# ProPrj_Circular_Weaving_2025-12-15.net
KiCad netlist of a schematic drawn in EasyEDA Pro
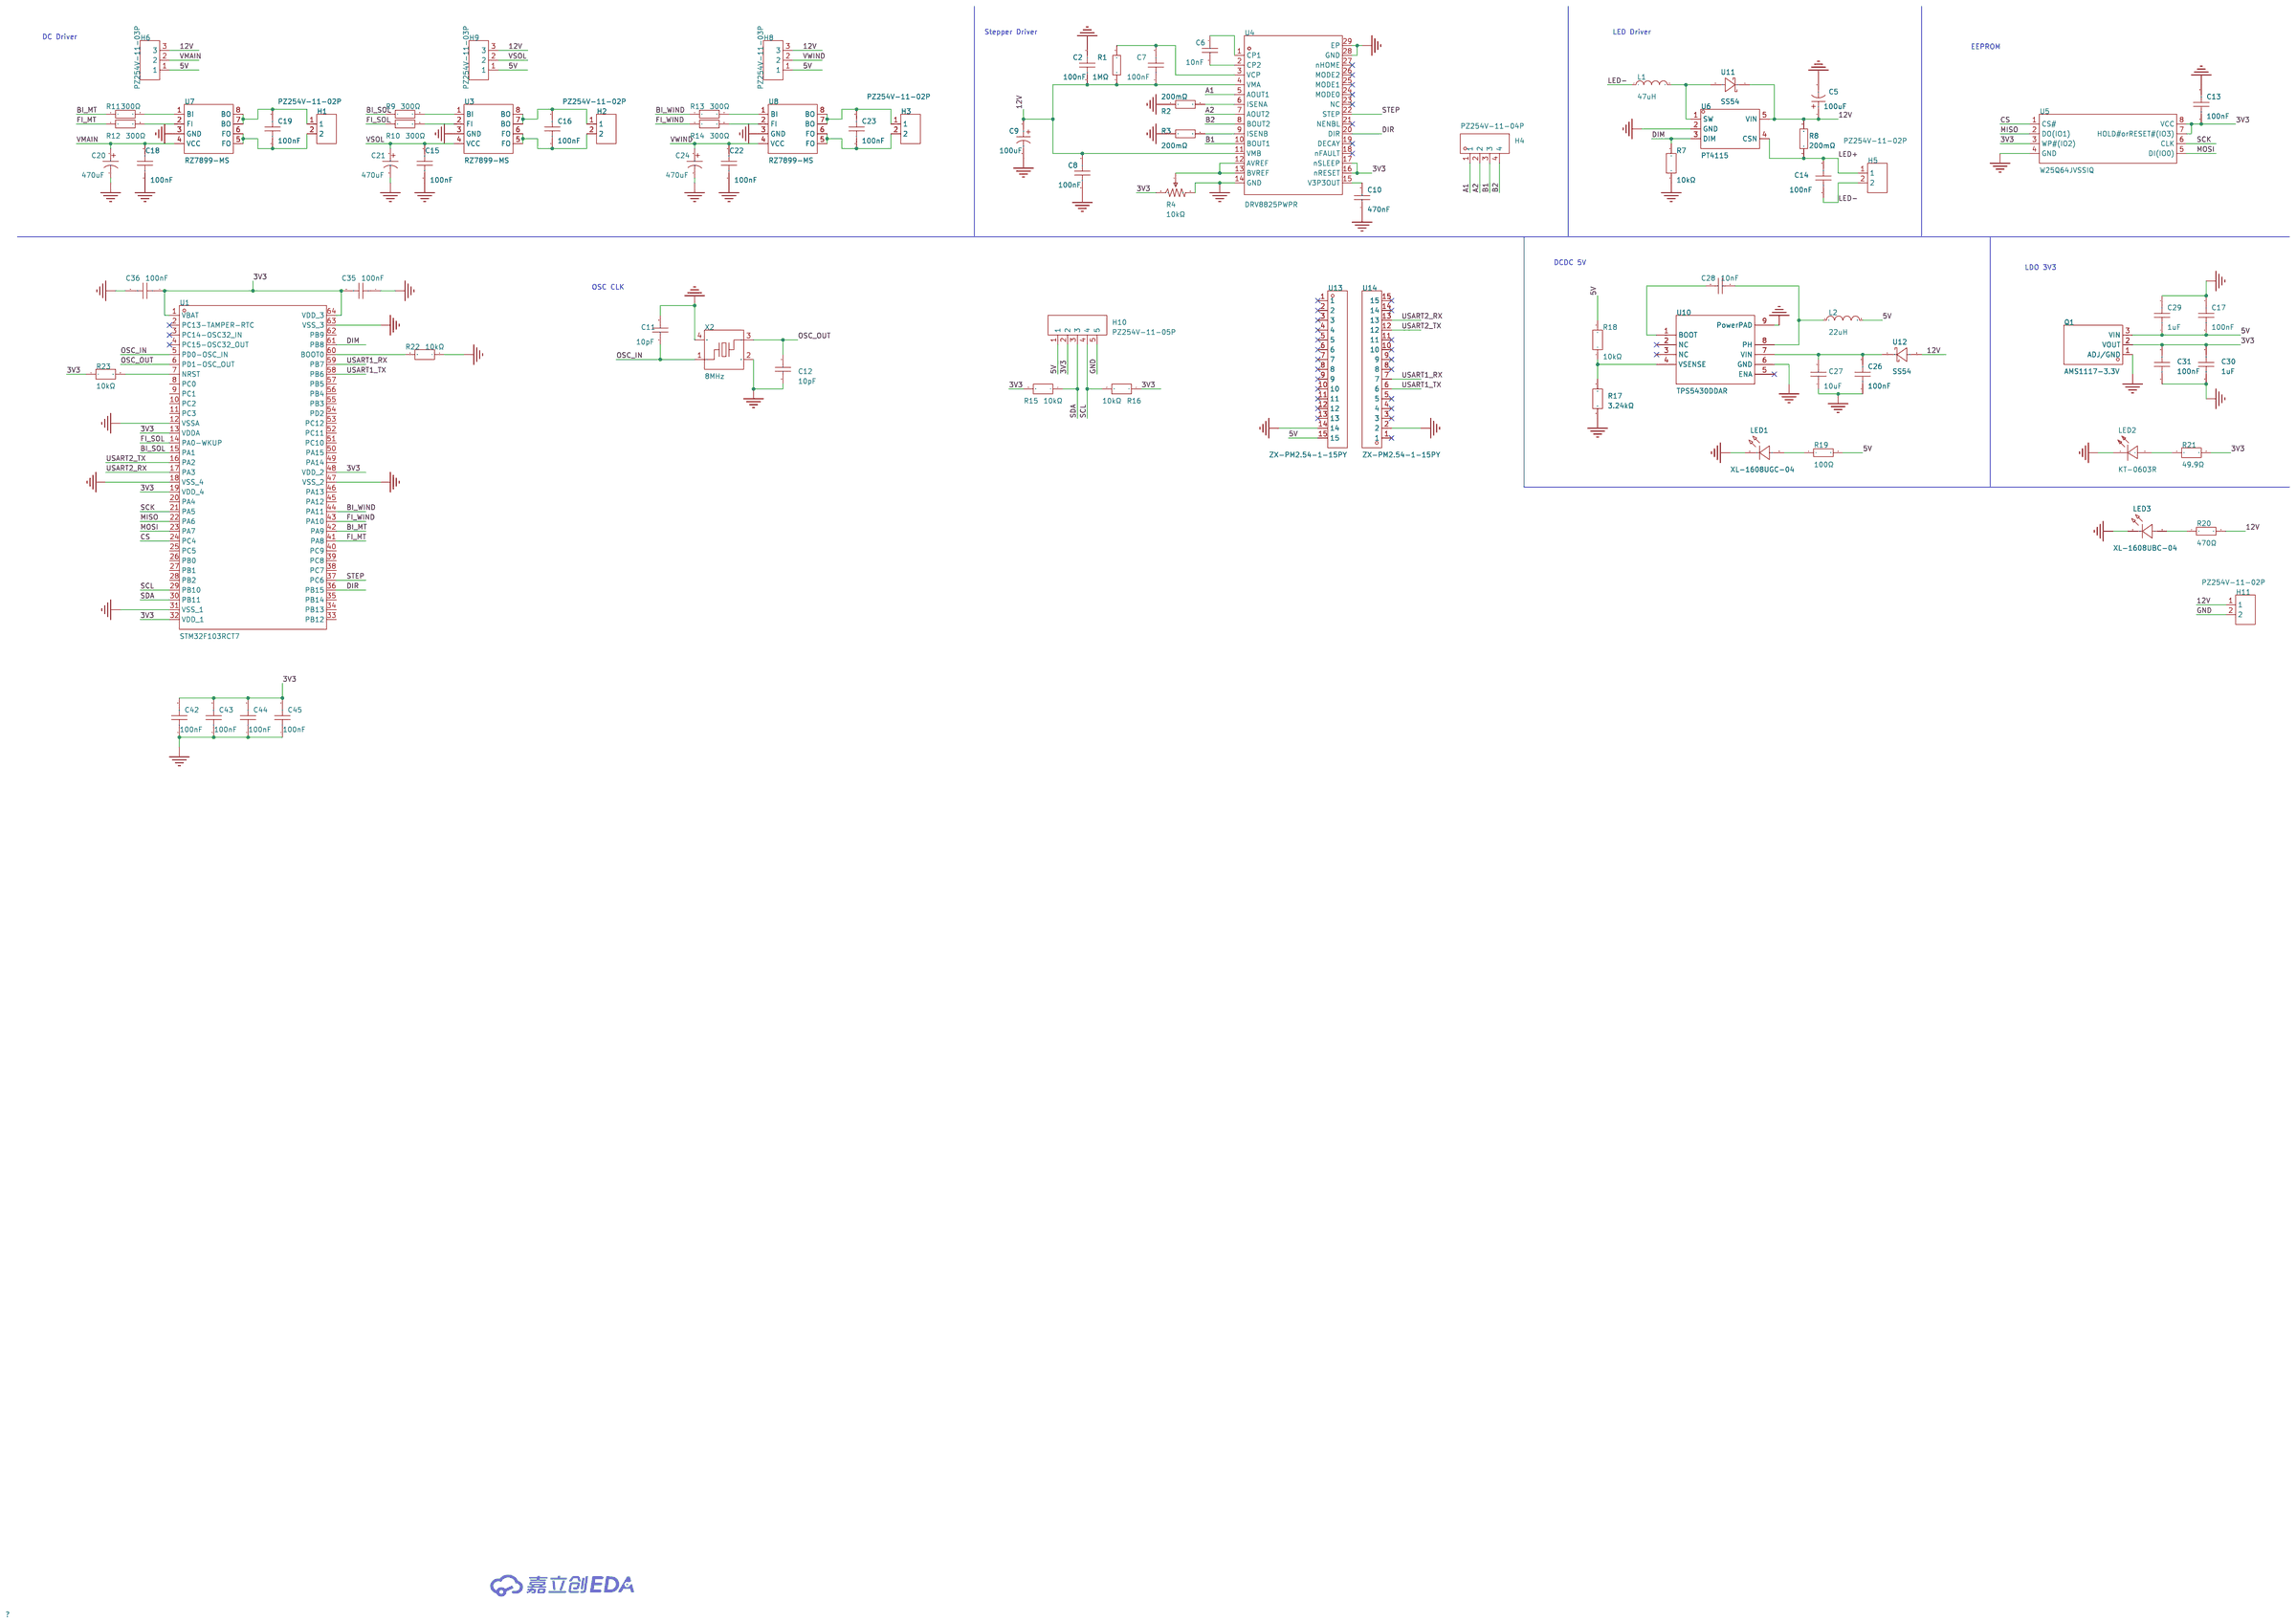
[diagram p0: schematic sheet]

(export (version "E")
  (design (tool "Eeschema 10.0.6"))
  (components
    (comp (ref "C2")
      (value "100nF")
      (footprint "easyedapro:C0603")
      (description "容值:100nF;精度:±10%;额定电压:50V;温度系数:X7R;")
      (fields
        (field (name "Manufacturer Part") "CL10B104KB8NNNC")
        (field (name "Manufacturer") "SAMSUNG(三星)")
      )
      (libsource (lib "easyedapro") (part "CL10B104KB8NNNC"))
    )
    (comp (ref "C5")
      (value "100uF")
      (footprint "easyedapro:CAP-SMD_BD6.3-L6.6-W6.6-LS7.3-FD-H7.7")
      (description "容值:100uF;精度:±20%;额定电压:50V;纹波电流:140mA@120Hz;")
      (fields (field (name "Manufacturer Part") "JVJ50V100M6x8") (field (name "Manufacturer") "JIERR(捷而瑞)"))
      (libsource (lib "easyedapro") (part "JVJ50V100M6X8"))
    )
    (comp (ref "C6")
      (value "10nF")
      (footprint "easyedapro:C0603")
      (description "容值:10nF;精度:±10%;额定电压:50V;温度系数:X7R;")
      (fields
        (field (name "Manufacturer Part") "CC0603KRX7R9BB103")
        (field (name "Manufacturer") "YAGEO(国巨)")
      )
      (libsource (lib "easyedapro") (part "CC0603KRX7R9BB103"))
    )
    (comp (ref "C7")
      (value "100nF")
      (footprint "easyedapro:C0603")
      (description "容值:100nF;精度:±10%;额定电压:50V;温度系数:X7R;")
      (fields
        (field (name "Manufacturer Part") "CL10B104KB8NNNC")
        (field (name "Manufacturer") "SAMSUNG(三星)")
      )
      (libsource (lib "easyedapro") (part "CL10B104KB8NNNC"))
    )
    (comp (ref "C8")
      (value "100nF")
      (footprint "easyedapro:C0603")
      (description "容值:100nF;精度:±10%;额定电压:50V;温度系数:X7R;")
      (fields
        (field (name "Manufacturer Part") "CL10B104KB8NNNC")
        (field (name "Manufacturer") "SAMSUNG(三星)")
      )
      (libsource (lib "easyedapro") (part "CL10B104KB8NNNC"))
    )
    (comp (ref "C9")
      (value "100uF")
      (footprint "easyedapro:CAP-SMD_BD6.3-L6.6-W6.6-LS7.3-FD-H7.7")
      (description "容值:100uF;精度:±20%;额定电压:50V;纹波电流:140mA@120Hz;")
      (fields (field (name "Manufacturer Part") "JVJ50V100M6x8") (field (name "Manufacturer") "JIERR(捷而瑞)"))
      (libsource (lib "easyedapro") (part "JVJ50V100M6X8"))
    )
    (comp (ref "C10")
      (value "470nF")
      (footprint "easyedapro:C0603")
      (description "容值:470nF;精度:±10%;额定电压:25V;温度系数:X7R;")
      (fields
        (field (name "Manufacturer Part") "CL10B474KA8NNNC")
        (field (name "Manufacturer") "SAMSUNG(三星)")
      )
      (libsource (lib "easyedapro") (part "CL10B474KA8NNNC"))
    )
    (comp (ref "C11")
      (value "10pF")
      (footprint "easyedapro:C0603")
      (description "容值:10pF;精度:±5%;额定电压:50V;温度系数:C0G;")
      (fields
        (field (name "Manufacturer Part") "CL10C100JB8NNNC")
        (field (name "Manufacturer") "SAMSUNG(三星)")
      )
      (libsource (lib "easyedapro") (part "CL10C100JB8NNNC"))
    )
    (comp (ref "C12")
      (value "10pF")
      (footprint "easyedapro:C0603")
      (description "容值:10pF;精度:±5%;额定电压:50V;温度系数:C0G;")
      (fields
        (field (name "Manufacturer Part") "CL10C100JB8NNNC")
        (field (name "Manufacturer") "SAMSUNG(三星)")
      )
      (libsource (lib "easyedapro") (part "CL10C100JB8NNNC"))
    )
    (comp (ref "C13")
      (value "100nF")
      (footprint "easyedapro:C0603")
      (description "容值:100nF;精度:±10%;额定电压:50V;温度系数:X7R;")
      (fields
        (field (name "Manufacturer Part") "CL10B104KB8NNNC")
        (field (name "Manufacturer") "SAMSUNG(三星)")
      )
      (libsource (lib "easyedapro") (part "CL10B104KB8NNNC"))
    )
    (comp (ref "C14")
      (value "100nF")
      (footprint "easyedapro:C0603")
      (description "容值:100nF;精度:±10%;额定电压:50V;温度系数:X7R;")
      (fields
        (field (name "Manufacturer Part") "CL10B104KB8NNNC")
        (field (name "Manufacturer") "SAMSUNG(三星)")
      )
      (libsource (lib "easyedapro") (part "CL10B104KB8NNNC"))
    )
    (comp (ref "C15")
      (value "100nF")
      (footprint "easyedapro:C0603")
      (description "容值:100nF;精度:±10%;额定电压:50V;温度系数:X7R;")
      (fields
        (field (name "Manufacturer Part") "CL10B104KB8NNNC")
        (field (name "Manufacturer") "SAMSUNG(三星)")
      )
      (libsource (lib "easyedapro") (part "CL10B104KB8NNNC"))
    )
    (comp (ref "C16")
      (value "100nF")
      (footprint "easyedapro:C0603")
      (description "容值:100nF;精度:±10%;额定电压:50V;温度系数:X7R;")
      (fields
        (field (name "Manufacturer Part") "CL10B104KB8NNNC")
        (field (name "Manufacturer") "SAMSUNG(三星)")
      )
      (libsource (lib "easyedapro") (part "CL10B104KB8NNNC"))
    )
    (comp (ref "C17")
      (value "100nF")
      (footprint "easyedapro:C0603")
      (description "容值:100nF;精度:±10%;额定电压:50V;温度系数:X7R;")
      (fields
        (field (name "Manufacturer Part") "CL10B104KB8NNNC")
        (field (name "Manufacturer") "SAMSUNG(三星)")
      )
      (libsource (lib "easyedapro") (part "CL10B104KB8NNNC"))
    )
    (comp (ref "C18")
      (value "100nF")
      (footprint "easyedapro:C0603")
      (description "容值:100nF;精度:±10%;额定电压:50V;温度系数:X7R;")
      (fields
        (field (name "Manufacturer Part") "CL10B104KB8NNNC")
        (field (name "Manufacturer") "SAMSUNG(三星)")
      )
      (libsource (lib "easyedapro") (part "CL10B104KB8NNNC"))
    )
    (comp (ref "C19")
      (value "100nF")
      (footprint "easyedapro:C0603")
      (description "容值:100nF;精度:±10%;额定电压:50V;温度系数:X7R;")
      (fields
        (field (name "Manufacturer Part") "CL10B104KB8NNNC")
        (field (name "Manufacturer") "SAMSUNG(三星)")
      )
      (libsource (lib "easyedapro") (part "CL10B104KB8NNNC"))
    )
    (comp (ref "C20")
      (value "470uF")
      (footprint "easyedapro:CAP-SMD_BD10.0-L10.3-W10.3-LS11.0-R-RD")
      (description "容值:470uF;精度:±20%;额定电压:35V;纹波电流:286mA@120Hz;等效串联电阻(ESR):-;")
      (fields (field (name "Manufacturer Part") "RVT1V471M1010") (field (name "Manufacturer") "ROQANG(容强)"))
      (libsource (lib "easyedapro") (part "RVT1V471M1010-C72519"))
    )
    (comp (ref "C21")
      (value "470uF")
      (footprint "easyedapro:CAP-SMD_BD10.0-L10.3-W10.3-LS11.0-R-RD")
      (description "容值:470uF;精度:±20%;额定电压:35V;纹波电流:286mA@120Hz;等效串联电阻(ESR):-;")
      (fields (field (name "Manufacturer Part") "RVT1V471M1010") (field (name "Manufacturer") "ROQANG(容强)"))
      (libsource (lib "easyedapro") (part "RVT1V471M1010-C72519"))
    )
    (comp (ref "C22")
      (value "100nF")
      (footprint "easyedapro:C0603")
      (description "容值:100nF;精度:±10%;额定电压:50V;温度系数:X7R;")
      (fields
        (field (name "Manufacturer Part") "CL10B104KB8NNNC")
        (field (name "Manufacturer") "SAMSUNG(三星)")
      )
      (libsource (lib "easyedapro") (part "CL10B104KB8NNNC"))
    )
    (comp (ref "C23")
      (value "100nF")
      (footprint "easyedapro:C0603")
      (description "容值:100nF;精度:±10%;额定电压:50V;温度系数:X7R;")
      (fields
        (field (name "Manufacturer Part") "CL10B104KB8NNNC")
        (field (name "Manufacturer") "SAMSUNG(三星)")
      )
      (libsource (lib "easyedapro") (part "CL10B104KB8NNNC"))
    )
    (comp (ref "C24")
      (value "470uF")
      (footprint "easyedapro:CAP-SMD_BD10.0-L10.3-W10.3-LS11.0-R-RD")
      (description "容值:470uF;精度:±20%;额定电压:35V;纹波电流:286mA@120Hz;等效串联电阻(ESR):-;")
      (fields (field (name "Manufacturer Part") "RVT1V471M1010") (field (name "Manufacturer") "ROQANG(容强)"))
      (libsource (lib "easyedapro") (part "RVT1V471M1010-C72519"))
    )
    (comp (ref "C26")
      (value "100nF")
      (footprint "easyedapro:C0603")
      (description "容值:100nF;精度:±10%;额定电压:50V;温度系数:X7R;")
      (fields
        (field (name "Manufacturer Part") "CL10B104KB8NNNC")
        (field (name "Manufacturer") "SAMSUNG(三星)")
      )
      (libsource (lib "easyedapro") (part "CL10B104KB8NNNC"))
    )
    (comp (ref "C27")
      (value "10uF")
      (footprint "easyedapro:C1206")
      (description "容值:10uF;精度:±10%;额定电压:50V;温度系数:X5R;")
      (fields
        (field (name "Manufacturer Part") "CL31A106KBHNNNE")
        (field (name "Manufacturer") "SAMSUNG(三星)")
      )
      (libsource (lib "easyedapro") (part "CL31A106KBHNNNE"))
    )
    (comp (ref "C28")
      (value "10nF")
      (footprint "easyedapro:C0603")
      (description "容值:10nF;精度:±10%;额定电压:50V;温度系数:X7R;")
      (fields
        (field (name "Manufacturer Part") "CC0603KRX7R9BB103")
        (field (name "Manufacturer") "YAGEO(国巨)")
      )
      (libsource (lib "easyedapro") (part "CC0603KRX7R9BB103"))
    )
    (comp (ref "C29")
      (value "1uF")
      (footprint "easyedapro:C0603")
      (description "容值:1uF;精度:±10%;额定电压:50V;温度系数:X5R;")
      (fields
        (field (name "Manufacturer Part") "CL10A105KB8NNNC")
        (field (name "Manufacturer") "SAMSUNG(三星)")
      )
      (libsource (lib "easyedapro") (part "CL10A105KB8NNNC"))
    )
    (comp (ref "C30")
      (value "1uF")
      (footprint "easyedapro:C0603")
      (description "容值:1uF;精度:±10%;额定电压:50V;温度系数:X5R;")
      (fields
        (field (name "Manufacturer Part") "CL10A105KB8NNNC")
        (field (name "Manufacturer") "SAMSUNG(三星)")
      )
      (libsource (lib "easyedapro") (part "CL10A105KB8NNNC"))
    )
    (comp (ref "C31")
      (value "100nF")
      (footprint "easyedapro:C0603")
      (description "容值:100nF;精度:±10%;额定电压:50V;温度系数:X7R;")
      (fields
        (field (name "Manufacturer Part") "CL10B104KB8NNNC")
        (field (name "Manufacturer") "SAMSUNG(三星)")
      )
      (libsource (lib "easyedapro") (part "CL10B104KB8NNNC"))
    )
    (comp (ref "C35")
      (value "100nF")
      (footprint "easyedapro:C0603")
      (description "容值:100nF;精度:±10%;额定电压:50V;温度系数:X7R;")
      (fields
        (field (name "Manufacturer Part") "CL10B104KB8NNNC")
        (field (name "Manufacturer") "SAMSUNG(三星)")
      )
      (libsource (lib "easyedapro") (part "CL10B104KB8NNNC"))
    )
    (comp (ref "C36")
      (value "100nF")
      (footprint "easyedapro:C0603")
      (description "容值:100nF;精度:±10%;额定电压:50V;温度系数:X7R;")
      (fields
        (field (name "Manufacturer Part") "CL10B104KB8NNNC")
        (field (name "Manufacturer") "SAMSUNG(三星)")
      )
      (libsource (lib "easyedapro") (part "CL10B104KB8NNNC"))
    )
    (comp (ref "C42")
      (value "100nF")
      (footprint "easyedapro:C0603")
      (description "容值:100nF;精度:±10%;额定电压:50V;温度系数:X7R;")
      (fields
        (field (name "Manufacturer Part") "CL10B104KB8NNNC")
        (field (name "Manufacturer") "SAMSUNG(三星)")
      )
      (libsource (lib "easyedapro") (part "CL10B104KB8NNNC"))
    )
    (comp (ref "C43")
      (value "100nF")
      (footprint "easyedapro:C0603")
      (description "容值:100nF;精度:±10%;额定电压:50V;温度系数:X7R;")
      (fields
        (field (name "Manufacturer Part") "CL10B104KB8NNNC")
        (field (name "Manufacturer") "SAMSUNG(三星)")
      )
      (libsource (lib "easyedapro") (part "CL10B104KB8NNNC"))
    )
    (comp (ref "C44")
      (value "100nF")
      (footprint "easyedapro:C0603")
      (description "容值:100nF;精度:±10%;额定电压:50V;温度系数:X7R;")
      (fields
        (field (name "Manufacturer Part") "CL10B104KB8NNNC")
        (field (name "Manufacturer") "SAMSUNG(三星)")
      )
      (libsource (lib "easyedapro") (part "CL10B104KB8NNNC"))
    )
    (comp (ref "C45")
      (value "100nF")
      (footprint "easyedapro:C0603")
      (description "容值:100nF;精度:±10%;额定电压:50V;温度系数:X7R;")
      (fields
        (field (name "Manufacturer Part") "CL10B104KB8NNNC")
        (field (name "Manufacturer") "SAMSUNG(三星)")
      )
      (libsource (lib "easyedapro") (part "CL10B104KB8NNNC"))
    )
    (comp (ref "H1")
      (value "PZ254V-11-02P")
      (footprint "easyedapro:HDR-TH_2P-P2.54-V-M")
      (fields (field (name "Manufacturer") "XFCN(兴飞)"))
      (libsource (lib "easyedapro") (part "PZ254V-11-02P"))
    )
    (comp (ref "H2")
      (value "PZ254V-11-02P")
      (footprint "easyedapro:HDR-TH_2P-P2.54-V-M")
      (fields (field (name "Manufacturer") "XFCN(兴飞)"))
      (libsource (lib "easyedapro") (part "PZ254V-11-02P"))
    )
    (comp (ref "H3")
      (value "PZ254V-11-02P")
      (footprint "easyedapro:HDR-TH_2P-P2.54-V-M")
      (fields (field (name "Manufacturer") "XFCN(兴飞)"))
      (libsource (lib "easyedapro") (part "PZ254V-11-02P"))
    )
    (comp (ref "H4")
      (value "PZ254V-11-04P")
      (footprint "easyedapro:HDR-TH_4P-P2.54-V-M")
      (fields (field (name "Manufacturer") "XFCN(兴飞)"))
      (libsource (lib "easyedapro") (part "PZ254V-11-04P_C2691448"))
    )
    (comp (ref "H5")
      (value "PZ254V-11-02P")
      (footprint "easyedapro:HDR-TH_2P-P2.54-V-M")
      (fields (field (name "Manufacturer") "XFCN(兴飞)"))
      (libsource (lib "easyedapro") (part "PZ254V-11-02P"))
    )
    (comp (ref "H6")
      (value "PZ254V-11-03P")
      (footprint "easyedapro:HDR-TH_3P-P2.54-V-M")
      (fields (field (name "Manufacturer") "XFCN(兴飞)"))
      (libsource (lib "easyedapro") (part "PZ254V-11-03P_C2937625"))
    )
    (comp (ref "H8")
      (value "PZ254V-11-03P")
      (footprint "easyedapro:HDR-TH_3P-P2.54-V-M")
      (fields (field (name "Manufacturer") "XFCN(兴飞)"))
      (libsource (lib "easyedapro") (part "PZ254V-11-03P_C2937625"))
    )
    (comp (ref "H9")
      (value "PZ254V-11-03P")
      (footprint "easyedapro:HDR-TH_3P-P2.54-V-M")
      (fields (field (name "Manufacturer") "XFCN(兴飞)"))
      (libsource (lib "easyedapro") (part "PZ254V-11-03P_C2937625"))
    )
    (comp (ref "H10")
      (value "PZ254V-11-05P")
      (footprint "easyedapro:HDR-TH_5P-P2.54-V-M")
      (fields (field (name "Manufacturer") "XFCN(兴飞)"))
      (libsource (lib "easyedapro") (part "PZ254V-11-05P"))
    )
    (comp (ref "H11")
      (value "PZ254V-11-02P")
      (footprint "easyedapro:HDR-TH_2P-P2.54-V-M")
      (fields (field (name "Manufacturer") "XFCN(兴飞)"))
      (libsource (lib "easyedapro") (part "PZ254V-11-02P"))
    )
    (comp (ref "L1")
      (value "47uH")
      (footprint "easyedapro:IND-SMD_L7.0-W6.6_FXL0630")
      (description "电感值:47uH;精度:±20%;额定电流:1.5A;饱和电流(Isat):2A;类型:一体成型电感;")
      (fields (field (name "Manufacturer Part") "FXL0630-470-M") (field (name "Manufacturer") "cjiang(长江微电)"))
      (libsource (lib "easyedapro") (part "FXL0630-470-M"))
    )
    (comp (ref "L2")
      (value "22uH")
      (footprint "easyedapro:IND-SMD_L7.1-W6.6")
      (description "电感值:22uH;精度:±20%;额定电流:3A;类型:一体成型电感;")
      (fields
        (field (name "Manufacturer Part") "YSPI0630A-220M")
        (field (name "Manufacturer") "YJYCOIN(益嘉源)")
      )
      (libsource (lib "easyedapro") (part "YSPI0630A-220M"))
    )
    (comp (ref "LED1")
      (value "XL-1608UGC-04")
      (footprint "easyedapro:LED0603-RD_GREEN")
      (fields (field (name "Manufacturer") "XINGLIGHT(成兴光)"))
      (libsource (lib "easyedapro") (part "XL-1608UGC-04"))
    )
    (comp (ref "LED2")
      (value "KT-0603R")
      (footprint "easyedapro:LED0603-RD")
      (description "发光颜色:红色;功率:-;正向电流:-;主波长:-;二极管配置:-;透镜颜色:-;色温:-;发光角度:-;载带方式:-;工作温度:-40°C~+85°C;")
      (fields (field (name "Manufacturer") "KENTO"))
      (libsource (lib "easyedapro") (part "KT-0603R"))
    )
    (comp (ref "LED3")
      (value "XL-1608UBC-04")
      (footprint "easyedapro:LED0603-RD_BLUE")
      (fields (field (name "Manufacturer") "XINGLIGHT(成兴光)"))
      (libsource (lib "easyedapro") (part "XL-1608UBC-04"))
    )
    (comp (ref "Q1")
      (value "AMS1117-3.3V")
      (footprint "easyedapro:SOT-89-3_L4.5-W2.5-P1.50-LS4.2-BR")
      (description "输出类型:固定;工作电压:18V;输出电压:3.3V;输出电流:1A;输出极性:正极;")
      (fields (field (name "Manufacturer") "MSKSEMI(美森科)"))
      (libsource (lib "easyedapro") (part "AMS1117-3.3V_C5120796"))
    )
    (comp (ref "R1")
      (value "1MΩ")
      (footprint "easyedapro:R0603")
      (description "电阻类型:厚膜电阻;阻值:1MΩ;精度:±1%;功率:100mW;最大工作电压:75V;温度系数:±100ppm/°C;")
      (fields
        (field (name "Manufacturer Part") "0603WAF1004T5E")
        (field (name "Manufacturer") "UNI-ROYAL(厚声)")
      )
      (libsource (lib "easyedapro") (part "0603WAF1004T5E"))
    )
    (comp (ref "R2")
      (value "200mΩ")
      (footprint "easyedapro:R0603")
      (description "电阻类型:厚膜电阻;阻值:200mΩ;精度:±1%;功率:100mW;工作电压:75V;温度系数:±800ppm/°C;")
      (fields
        (field (name "Manufacturer Part") "0603WAF200LT5E")
        (field (name "Manufacturer") "UNI-ROYAL(厚声)")
      )
      (libsource (lib "easyedapro") (part "0603WAF200LT5E"))
    )
    (comp (ref "R3")
      (value "200mΩ")
      (footprint "easyedapro:R0603")
      (description "电阻类型:厚膜电阻;阻值:200mΩ;精度:±1%;功率:100mW;工作电压:75V;温度系数:±800ppm/°C;")
      (fields
        (field (name "Manufacturer Part") "0603WAF200LT5E")
        (field (name "Manufacturer") "UNI-ROYAL(厚声)")
      )
      (libsource (lib "easyedapro") (part "0603WAF200LT5E"))
    )
    (comp (ref "R4")
      (value "10kΩ")
      (footprint "easyedapro:RES-ADJ-SMD_JER33X-1-14")
      (description "阻值:10kΩ;精度:±25%;功率:150mW;温度系数:±250ppm/°C;")
      (fields (field (name "Manufacturer Part") "JER33X-1-14") (field (name "Manufacturer") "JIERR(捷而瑞)"))
      (libsource (lib "easyedapro") (part "JER33X-1-14"))
    )
    (comp (ref "R7")
      (value "10kΩ")
      (footprint "easyedapro:R0603")
      (description "电阻类型:厚膜电阻;阻值:10kΩ;精度:±5%;功率:100mW;工作电压:75V;温度系数:±100ppm/°C;")
      (fields (field (name "Manufacturer Part") "FRC0603J103 TS") (field (name "Manufacturer") "FOJAN(富捷)"))
      (libsource (lib "easyedapro") (part "FRC0603J103TS"))
    )
    (comp (ref "R8")
      (value "200mΩ")
      (footprint "easyedapro:R0603")
      (description "电阻类型:厚膜电阻;阻值:200mΩ;精度:±1%;功率:100mW;工作电压:75V;温度系数:±800ppm/°C;")
      (fields
        (field (name "Manufacturer Part") "0603WAF200LT5E")
        (field (name "Manufacturer") "UNI-ROYAL(厚声)")
      )
      (libsource (lib "easyedapro") (part "0603WAF200LT5E"))
    )
    (comp (ref "R9")
      (value "300Ω")
      (footprint "easyedapro:R0603")
      (description "电阻类型:厚膜电阻;阻值:300Ω;精度:±1%;功率:100mW;工作电压:75V;温度系数:±100ppm/°C;")
      (fields
        (field (name "Manufacturer Part") "0603WAF3000T5E")
        (field (name "Manufacturer") "UNI-ROYAL(厚声)")
      )
      (libsource (lib "easyedapro") (part "0603WAF3000T5E"))
    )
    (comp (ref "R10")
      (value "300Ω")
      (footprint "easyedapro:R0603")
      (description "电阻类型:厚膜电阻;阻值:300Ω;精度:±1%;功率:100mW;工作电压:75V;温度系数:±100ppm/°C;")
      (fields
        (field (name "Manufacturer Part") "0603WAF3000T5E")
        (field (name "Manufacturer") "UNI-ROYAL(厚声)")
      )
      (libsource (lib "easyedapro") (part "0603WAF3000T5E"))
    )
    (comp (ref "R11")
      (value "300Ω")
      (footprint "easyedapro:R0603")
      (description "电阻类型:厚膜电阻;阻值:300Ω;精度:±1%;功率:100mW;工作电压:75V;温度系数:±100ppm/°C;")
      (fields
        (field (name "Manufacturer Part") "0603WAF3000T5E")
        (field (name "Manufacturer") "UNI-ROYAL(厚声)")
      )
      (libsource (lib "easyedapro") (part "0603WAF3000T5E"))
    )
    (comp (ref "R12")
      (value "300Ω")
      (footprint "easyedapro:R0603")
      (description "电阻类型:厚膜电阻;阻值:300Ω;精度:±1%;功率:100mW;工作电压:75V;温度系数:±100ppm/°C;")
      (fields
        (field (name "Manufacturer Part") "0603WAF3000T5E")
        (field (name "Manufacturer") "UNI-ROYAL(厚声)")
      )
      (libsource (lib "easyedapro") (part "0603WAF3000T5E"))
    )
    (comp (ref "R13")
      (value "300Ω")
      (footprint "easyedapro:R0603")
      (description "电阻类型:厚膜电阻;阻值:300Ω;精度:±1%;功率:100mW;工作电压:75V;温度系数:±100ppm/°C;")
      (fields
        (field (name "Manufacturer Part") "0603WAF3000T5E")
        (field (name "Manufacturer") "UNI-ROYAL(厚声)")
      )
      (libsource (lib "easyedapro") (part "0603WAF3000T5E"))
    )
    (comp (ref "R14")
      (value "300Ω")
      (footprint "easyedapro:R0603")
      (description "电阻类型:厚膜电阻;阻值:300Ω;精度:±1%;功率:100mW;工作电压:75V;温度系数:±100ppm/°C;")
      (fields
        (field (name "Manufacturer Part") "0603WAF3000T5E")
        (field (name "Manufacturer") "UNI-ROYAL(厚声)")
      )
      (libsource (lib "easyedapro") (part "0603WAF3000T5E"))
    )
    (comp (ref "R15")
      (value "10kΩ")
      (footprint "easyedapro:R0603")
      (description "电阻类型:厚膜电阻;阻值:10kΩ;精度:±5%;功率:100mW;工作电压:75V;温度系数:±100ppm/°C;")
      (fields (field (name "Manufacturer Part") "FRC0603J103 TS") (field (name "Manufacturer") "FOJAN(富捷)"))
      (libsource (lib "easyedapro") (part "FRC0603J103TS"))
    )
    (comp (ref "R16")
      (value "10kΩ")
      (footprint "easyedapro:R0603")
      (description "电阻类型:厚膜电阻;阻值:10kΩ;精度:±5%;功率:100mW;工作电压:75V;温度系数:±100ppm/°C;")
      (fields (field (name "Manufacturer Part") "FRC0603J103 TS") (field (name "Manufacturer") "FOJAN(富捷)"))
      (libsource (lib "easyedapro") (part "FRC0603J103TS"))
    )
    (comp (ref "R17")
      (value "3.24kΩ")
      (footprint "easyedapro:R0603")
      (description "电阻类型:厚膜电阻;阻值:3.24kΩ;精度:±1%;功率:100mW;工作电压:75V;温度系数:±100ppm/°C;")
      (fields (field (name "Manufacturer Part") "FRC0603F3241TS") (field (name "Manufacturer") "FOJAN(富捷)"))
      (libsource (lib "easyedapro") (part "FRC0603F3241TS"))
    )
    (comp (ref "R18")
      (value "10kΩ")
      (footprint "easyedapro:R0603")
      (description "电阻类型:厚膜电阻;阻值:10kΩ;精度:±5%;功率:100mW;工作电压:75V;温度系数:±100ppm/°C;")
      (fields (field (name "Manufacturer Part") "FRC0603J103 TS") (field (name "Manufacturer") "FOJAN(富捷)"))
      (libsource (lib "easyedapro") (part "FRC0603J103TS"))
    )
    (comp (ref "R19")
      (value "100Ω")
      (footprint "easyedapro:R0603")
      (description "电阻类型:厚膜电阻;阻值:100Ω;精度:±1%;功率:100mW;最大工作电压:75V;温度系数:±200ppm/°C;")
      (fields
        (field (name "Manufacturer Part") "0603WAF1000T5E")
        (field (name "Manufacturer") "UNI-ROYAL(厚声)")
      )
      (libsource (lib "easyedapro") (part "0603WAF1000T5E"))
    )
    (comp (ref "R20")
      (value "470Ω")
      (footprint "easyedapro:R0603")
      (description "电阻类型:厚膜电阻;阻值:470Ω;精度:±1%;功率:100mW;工作电压:75V;温度系数:±100ppm/°C;")
      (fields
        (field (name "Manufacturer Part") "0603WAF4700T5E")
        (field (name "Manufacturer") "UNI-ROYAL(厚声)")
      )
      (libsource (lib "easyedapro") (part "0603WAF4700T5E"))
    )
    (comp (ref "R21")
      (value "49.9Ω")
      (footprint "easyedapro:R0603")
      (description "电阻类型:厚膜电阻;阻值:49.9Ω;精度:±1%;功率:100mW;工作电压:75V;温度系数:±100ppm/°C;")
      (fields (field (name "Manufacturer Part") "FRC0603F49R9TS") (field (name "Manufacturer") "FOJAN(富捷)"))
      (libsource (lib "easyedapro") (part "FRC0603F49R9TS"))
    )
    (comp (ref "R22")
      (value "10kΩ")
      (footprint "easyedapro:R0603")
      (description "电阻类型:厚膜电阻;阻值:10kΩ;精度:±5%;功率:100mW;工作电压:75V;温度系数:±100ppm/°C;")
      (fields (field (name "Manufacturer Part") "FRC0603J103 TS") (field (name "Manufacturer") "FOJAN(富捷)"))
      (libsource (lib "easyedapro") (part "FRC0603J103TS"))
    )
    (comp (ref "R23")
      (value "10kΩ")
      (footprint "easyedapro:R0603")
      (description "电阻类型:厚膜电阻;阻值:10kΩ;精度:±5%;功率:100mW;工作电压:75V;温度系数:±100ppm/°C;")
      (fields (field (name "Manufacturer Part") "FRC0603J103 TS") (field (name "Manufacturer") "FOJAN(富捷)"))
      (libsource (lib "easyedapro") (part "FRC0603J103TS"))
    )
    (comp (ref "U1")
      (value "STM32F103RCT7")
      (footprint "easyedapro:LQFP-64_L10.0-W10.0-P0.50-LS12.0-BL")
      (description "CPU内核:ARM-M3;CPU最大主频:72MHz;应用领域:-;")
      (fields (field (name "Manufacturer") "ST(意法半导体)"))
      (libsource (lib "easyedapro") (part "STM32F103RCT7"))
    )
    (comp (ref "U3")
      (value "RZ7899-MS")
      (footprint "easyedapro:SOIC-8_L4.9-W3.9-P1.27-LS6.0-BL")
      (fields (field (name "Manufacturer") "MSKSEMI(美森科)"))
      (libsource (lib "easyedapro") (part "RZ7899-MS"))
    )
    (comp (ref "U4")
      (value "DRV8825PWPR")
      (footprint "easyedapro:HTSSOP-28_L9.7-W4.4-P0.65-LS6.4-BL-EP")
      (description "DRV8825 具有电流调节功能和 1/32 微步进的 45V、2.5A 双极步进电机驱动器")
      (fields (field (name "Manufacturer") "TI(德州仪器)"))
      (libsource (lib "easyedapro") (part "DRV8825PWPR"))
    )
    (comp (ref "U5")
      (value "W25Q64JVSSIQ")
      (footprint "easyedapro:SOIC-8_L5.3-W5.3-P1.27-LS8.0-BL")
      (description "接口类型:SPI;存储容量:64Mbit;时钟频率(fc):133MHz;")
      (fields (field (name "Manufacturer") "Winbond(华邦)"))
      (libsource (lib "easyedapro") (part "W25Q64JVSSIQ_C179171"))
    )
    (comp (ref "U6")
      (value "PT4115")
      (footprint "easyedapro:SOT-89-5_L4.5-W2.5-P1.50-LS4.5-BR")
      (description "类型:-;输入电压:-;开关频率:-;通道数:-;输出电压:-;输出电流:-;调光:-;")
      (fields (field (name "Manufacturer") "UMW(友台半导体)"))
      (libsource (lib "easyedapro") (part "PT4115"))
    )
    (comp (ref "U7")
      (value "RZ7899-MS")
      (footprint "easyedapro:SOIC-8_L4.9-W3.9-P1.27-LS6.0-BL")
      (fields (field (name "Manufacturer") "MSKSEMI(美森科)"))
      (libsource (lib "easyedapro") (part "RZ7899-MS"))
    )
    (comp (ref "U8")
      (value "RZ7899-MS")
      (footprint "easyedapro:SOIC-8_L4.9-W3.9-P1.27-LS6.0-BL")
      (fields (field (name "Manufacturer") "MSKSEMI(美森科)"))
      (libsource (lib "easyedapro") (part "RZ7899-MS"))
    )
    (comp (ref "U10")
      (value "TPS5430DDAR")
      (footprint "easyedapro:ESOP-8_L4.9-W3.9-P1.27-LS6.0-TL-EP")
      (description "功能类型:降压型;工作电压:5.5V~36V;输出电压:1.221V~32.04V;输出电流:3A;输出类型:可调;")
      (fields (field (name "Manufacturer") "TI(德州仪器)"))
      (libsource (lib "easyedapro") (part "TPS5430DDAR"))
    )
    (comp (ref "U11")
      (value "SS54")
      (footprint "easyedapro:SMB_L4.3-W3.6-LS5.4-RD")
      (description "二极管配置:独立式;正向压降(Vf):550mV@5A;直流反向耐压(Vr):40V;整流电流:5A;")
      (fields (field (name "Manufacturer") "HXY MOSFET(华轩阳电子)"))
      (libsource (lib "easyedapro") (part "SS54_C5200096"))
    )
    (comp (ref "U12")
      (value "SS54")
      (footprint "easyedapro:SMB_L4.3-W3.6-LS5.4-RD")
      (description "二极管配置:独立式;正向压降(Vf):550mV@5A;直流反向耐压(Vr):40V;整流电流:5A;")
      (fields (field (name "Manufacturer") "HXY MOSFET(华轩阳电子)"))
      (libsource (lib "easyedapro") (part "SS54_C5200096"))
    )
    (comp (ref "U13")
      (value "ZX-PM2.54-1-15PY")
      (footprint "easyedapro:HDR-TH_15P-P2.54-V-F")
      (fields (field (name "Manufacturer") "Megastar(兆星)"))
      (libsource (lib "easyedapro") (part "ZX-PM2.54-1-15PY"))
    )
    (comp (ref "U14")
      (value "ZX-PM2.54-1-15PY")
      (footprint "easyedapro:HDR-TH_15P-P2.54-V-F")
      (fields (field (name "Manufacturer") "Megastar(兆星)"))
      (libsource (lib "easyedapro") (part "ZX-PM2.54-1-15PY"))
    )
    (comp (ref "X2")
      (value "8MHz")
      (footprint "easyedapro:CRYSTAL-SMD_4P-L3.2-W2.5-BL")
      (description "晶振类型:贴片晶振;频率:8MHz;常温频差:±10ppm;负载电容:20pF;频率稳定度:±20ppm;")
      (fields
        (field (name "Manufacturer Part") "XL2EL89CSI-KPIYLC-8M")
        (field (name "Manufacturer") "YXC(扬兴晶振)")
      )
      (libsource (lib "easyedapro") (part "XL2EL89CSI-KPIYLC-8M"))
    )
  )
  (nets
    (net (code "1") (name "/3V3") (class "Default")
      (node (ref "C13") (pin "1") (pinfunction "1_1") (pintype "unspecified"))
      (node (ref "C30") (pin "1") (pinfunction "1_1") (pintype "unspecified"))
      (node (ref "C31") (pin "2") (pinfunction "2_2") (pintype "unspecified"))
      (node (ref "C35") (pin "2") (pinfunction "2_2") (pintype "unspecified"))
      (node (ref "C36") (pin "1") (pinfunction "1_1") (pintype "unspecified"))
      (node (ref "C42") (pin "2") (pinfunction "2_2") (pintype "unspecified"))
      (node (ref "C43") (pin "2") (pinfunction "2_2") (pintype "unspecified"))
      (node (ref "C44") (pin "2") (pinfunction "2_2") (pintype "unspecified"))
      (node (ref "C45") (pin "2") (pinfunction "2_2") (pintype "unspecified"))
      (node (ref "H10") (pin "2") (pinfunction "2_2") (pintype "unspecified"))
      (node (ref "Q1") (pin "2") (pinfunction "VOUT_2") (pintype "unspecified"))
      (node (ref "R15") (pin "2") (pinfunction "2_2") (pintype "unspecified"))
      (node (ref "R16") (pin "1") (pinfunction "1_1") (pintype "unspecified"))
      (node (ref "R21") (pin "2") (pinfunction "2_2") (pintype "unspecified"))
      (node (ref "R23") (pin "1") (pinfunction "1_1") (pintype "unspecified"))
      (node (ref "R4") (pin "3") (pinfunction "3_3") (pintype "unspecified"))
      (node (ref "U1") (pin "1") (pinfunction "VBAT_1") (pintype "unspecified"))
      (node (ref "U1") (pin "13") (pinfunction "VDDA_13") (pintype "unspecified"))
      (node (ref "U1") (pin "19") (pinfunction "VDD_4_19") (pintype "unspecified"))
      (node (ref "U1") (pin "32") (pinfunction "VDD_1_32") (pintype "unspecified"))
      (node (ref "U1") (pin "48") (pinfunction "VDD_2_48") (pintype "unspecified"))
      (node (ref "U1") (pin "64") (pinfunction "VDD_3_64") (pintype "unspecified"))
      (node (ref "U4") (pin "16") (pinfunction "nRESET_16") (pintype "unspecified"))
      (node (ref "U4") (pin "17") (pinfunction "nSLEEP_17") (pintype "unspecified"))
      (node (ref "U5") (pin "3") (pinfunction "WP#(IO2)_3") (pintype "unspecified"))
      (node (ref "U5") (pin "7") (pinfunction "HOLD#orRESET#(IO3)_7") (pintype "unspecified"))
      (node (ref "U5") (pin "8") (pinfunction "VCC_8") (pintype "unspecified"))
    )
    (net (code "2") (name "/5V") (class "Default")
      (node (ref "C17") (pin "2") (pinfunction "2_2") (pintype "unspecified"))
      (node (ref "C29") (pin "1") (pinfunction "1_1") (pintype "unspecified"))
      (node (ref "H10") (pin "1") (pinfunction "1_1") (pintype "unspecified"))
      (node (ref "H6") (pin "1") (pinfunction "1_1") (pintype "unspecified"))
      (node (ref "H8") (pin "1") (pinfunction "1_1") (pintype "unspecified"))
      (node (ref "H9") (pin "1") (pinfunction "1_1") (pintype "unspecified"))
      (node (ref "L2") (pin "2") (pinfunction "2_2") (pintype "unspecified"))
      (node (ref "Q1") (pin "3") (pinfunction "VIN_3") (pintype "unspecified"))
      (node (ref "R18") (pin "2") (pinfunction "2_2") (pintype "unspecified"))
      (node (ref "R19") (pin "2") (pinfunction "2_2") (pintype "input"))
      (node (ref "U13") (pin "15") (pinfunction "15_15") (pintype "unspecified"))
    )
    (net (code "3") (name "/12V") (class "Default")
      (node (ref "C2") (pin "2") (pinfunction "2_2") (pintype "unspecified"))
      (node (ref "C5") (pin "1") (pinfunction "1_1") (pintype "input"))
      (node (ref "C7") (pin "1") (pinfunction "1_1") (pintype "unspecified"))
      (node (ref "C8") (pin "1") (pinfunction "1_1") (pintype "unspecified"))
      (node (ref "C9") (pin "1") (pinfunction "1_1") (pintype "input"))
      (node (ref "H11") (pin "1") (pinfunction "1_1") (pintype "unspecified"))
      (node (ref "H6") (pin "3") (pinfunction "3_3") (pintype "unspecified"))
      (node (ref "H8") (pin "3") (pinfunction "3_3") (pintype "unspecified"))
      (node (ref "H9") (pin "3") (pinfunction "3_3") (pintype "unspecified"))
      (node (ref "R1") (pin "1") (pinfunction "1_1") (pintype "input"))
      (node (ref "R20") (pin "2") (pinfunction "2_2") (pintype "input"))
      (node (ref "R8") (pin "2") (pinfunction "2_2") (pintype "unspecified"))
      (node (ref "U11") (pin "1") (pinfunction "1_1") (pintype "unspecified"))
      (node (ref "U12") (pin "2") (pinfunction "2_2") (pintype "unspecified"))
      (node (ref "U4") (pin "11") (pinfunction "VMB_11") (pintype "unspecified"))
      (node (ref "U4") (pin "4") (pinfunction "VMA_4") (pintype "unspecified"))
      (node (ref "U6") (pin "5") (pinfunction "VIN_5") (pintype "unspecified"))
    )
    (net (code "4") (name "/A1") (class "Default")
      (node (ref "H4") (pin "1") (pinfunction "1_1") (pintype "unspecified"))
      (node (ref "U4") (pin "5") (pinfunction "AOUT1_5") (pintype "unspecified"))
    )
    (net (code "5") (name "/A2") (class "Default")
      (node (ref "H4") (pin "2") (pinfunction "2_2") (pintype "unspecified"))
      (node (ref "U4") (pin "7") (pinfunction "AOUT2_7") (pintype "unspecified"))
    )
    (net (code "6") (name "/B1") (class "Default")
      (node (ref "H4") (pin "3") (pinfunction "3_3") (pintype "unspecified"))
      (node (ref "U4") (pin "10") (pinfunction "BOUT1_10") (pintype "unspecified"))
    )
    (net (code "7") (name "/B2") (class "Default")
      (node (ref "H4") (pin "4") (pinfunction "4_4") (pintype "unspecified"))
      (node (ref "U4") (pin "8") (pinfunction "BOUT2_8") (pintype "unspecified"))
    )
    (net (code "8") (name "/BI_MT") (class "Default")
      (node (ref "R11") (pin "1") (pinfunction "1_1") (pintype "input"))
      (node (ref "U1") (pin "42") (pinfunction "PA9_42") (pintype "unspecified"))
    )
    (net (code "9") (name "/BI_SOL") (class "Default")
      (node (ref "R9") (pin "1") (pinfunction "1_1") (pintype "input"))
      (node (ref "U1") (pin "15") (pinfunction "PA1_15") (pintype "unspecified"))
    )
    (net (code "10") (name "/BI_WIND") (class "Default")
      (node (ref "R13") (pin "1") (pinfunction "1_1") (pintype "input"))
      (node (ref "U1") (pin "44") (pinfunction "PA11_44") (pintype "unspecified"))
    )
    (net (code "11") (name "/CS") (class "Default")
      (node (ref "U1") (pin "24") (pinfunction "PC4_24") (pintype "unspecified"))
      (node (ref "U5") (pin "1") (pinfunction "CS#_1") (pintype "unspecified"))
    )
    (net (code "12") (name "/DIM") (class "Default")
      (node (ref "R7") (pin "2") (pinfunction "2_2") (pintype "unspecified"))
      (node (ref "U1") (pin "61") (pinfunction "PB8_61") (pintype "unspecified"))
      (node (ref "U6") (pin "3") (pinfunction "DIM_3") (pintype "unspecified"))
    )
    (net (code "13") (name "/DIR") (class "Default")
      (node (ref "U1") (pin "36") (pinfunction "PB15_36") (pintype "unspecified"))
      (node (ref "U4") (pin "20") (pinfunction "DIR_20") (pintype "unspecified"))
    )
    (net (code "14") (name "/FI_MT") (class "Default")
      (node (ref "R12") (pin "1") (pinfunction "1_1") (pintype "input"))
      (node (ref "U1") (pin "41") (pinfunction "PA8_41") (pintype "unspecified"))
    )
    (net (code "15") (name "/FI_SOL") (class "Default")
      (node (ref "R10") (pin "1") (pinfunction "1_1") (pintype "input"))
      (node (ref "U1") (pin "14") (pinfunction "PA0-WKUP_14") (pintype "unspecified"))
    )
    (net (code "16") (name "/FI_WIND") (class "Default")
      (node (ref "R14") (pin "1") (pinfunction "1_1") (pintype "input"))
      (node (ref "U1") (pin "43") (pinfunction "PA10_43") (pintype "unspecified"))
    )
    (net (code "17") (name "/LED+") (class "Default")
      (node (ref "C14") (pin "2") (pinfunction "2_2") (pintype "unspecified"))
      (node (ref "H5") (pin "1") (pinfunction "1_1") (pintype "unspecified"))
      (node (ref "R8") (pin "1") (pinfunction "1_1") (pintype "unspecified"))
      (node (ref "U6") (pin "4") (pinfunction "CSN_4") (pintype "unspecified"))
    )
    (net (code "18") (name "/LED-") (class "Default")
      (node (ref "C14") (pin "1") (pinfunction "1_1") (pintype "unspecified"))
      (node (ref "H5") (pin "2") (pinfunction "2_2") (pintype "unspecified"))
      (node (ref "L1") (pin "1") (pinfunction "1_1") (pintype "unspecified"))
    )
    (net (code "19") (name "/MISO") (class "Default")
      (node (ref "U1") (pin "22") (pinfunction "PA6_22") (pintype "unspecified"))
      (node (ref "U5") (pin "2") (pinfunction "DO(IO1)_2") (pintype "unspecified"))
    )
    (net (code "20") (name "/MOSI") (class "Default")
      (node (ref "U1") (pin "23") (pinfunction "PA7_23") (pintype "unspecified"))
      (node (ref "U5") (pin "5") (pinfunction "DI(IO0)_5") (pintype "unspecified"))
    )
    (net (code "21") (name "/OSC_IN") (class "Default")
      (node (ref "C11") (pin "1") (pinfunction "1_1") (pintype "input"))
      (node (ref "U1") (pin "5") (pinfunction "PD0-OSC_IN_5") (pintype "unspecified"))
      (node (ref "X2") (pin "1") (pinfunction "1_1") (pintype "input"))
    )
    (net (code "22") (name "/OSC_OUT") (class "Default")
      (node (ref "C12") (pin "2") (pinfunction "2_2") (pintype "input"))
      (node (ref "U1") (pin "6") (pinfunction "PD1-OSC_OUT_6") (pintype "unspecified"))
      (node (ref "X2") (pin "3") (pinfunction "3_3") (pintype "input"))
    )
    (net (code "23") (name "/SCK") (class "Default")
      (node (ref "U1") (pin "21") (pinfunction "PA5_21") (pintype "unspecified"))
      (node (ref "U5") (pin "6") (pinfunction "CLK_6") (pintype "unspecified"))
    )
    (net (code "24") (name "/SCL") (class "Default")
      (node (ref "H10") (pin "4") (pinfunction "4_4") (pintype "unspecified"))
      (node (ref "R16") (pin "2") (pinfunction "2_2") (pintype "unspecified"))
      (node (ref "U1") (pin "29") (pinfunction "PB10_29") (pintype "unspecified"))
    )
    (net (code "25") (name "/SDA") (class "Default")
      (node (ref "H10") (pin "3") (pinfunction "3_3") (pintype "unspecified"))
      (node (ref "R15") (pin "1") (pinfunction "1_1") (pintype "unspecified"))
      (node (ref "U1") (pin "30") (pinfunction "PB11_30") (pintype "unspecified"))
    )
    (net (code "26") (name "/STEP") (class "Default")
      (node (ref "U1") (pin "37") (pinfunction "PC6_37") (pintype "unspecified"))
      (node (ref "U4") (pin "22") (pinfunction "STEP_22") (pintype "unspecified"))
    )
    (net (code "27") (name "/USART1_RX") (class "Default")
      (node (ref "U1") (pin "59") (pinfunction "PB7_59") (pintype "unspecified"))
      (node (ref "U14") (pin "7") (pinfunction "7_7") (pintype "unspecified"))
    )
    (net (code "28") (name "/USART1_TX") (class "Default")
      (node (ref "U1") (pin "58") (pinfunction "PB6_58") (pintype "unspecified"))
      (node (ref "U14") (pin "6") (pinfunction "6_6") (pintype "unspecified"))
    )
    (net (code "29") (name "/USART2_RX") (class "Default")
      (node (ref "U1") (pin "17") (pinfunction "PA3_17") (pintype "unspecified"))
      (node (ref "U14") (pin "13") (pinfunction "13_13") (pintype "unspecified"))
    )
    (net (code "30") (name "/USART2_TX") (class "Default")
      (node (ref "U1") (pin "16") (pinfunction "PA2_16") (pintype "unspecified"))
      (node (ref "U14") (pin "12") (pinfunction "12_12") (pintype "unspecified"))
    )
    (net (code "31") (name "/VMAIN") (class "Default")
      (node (ref "C18") (pin "2") (pinfunction "2_2") (pintype "unspecified"))
      (node (ref "C20") (pin "1") (pinfunction "1_1") (pintype "input"))
      (node (ref "H6") (pin "2") (pinfunction "2_2") (pintype "unspecified"))
      (node (ref "U7") (pin "4") (pinfunction "VCC_4") (pintype "unspecified"))
    )
    (net (code "32") (name "/VSOL") (class "Default")
      (node (ref "C15") (pin "2") (pinfunction "2_2") (pintype "unspecified"))
      (node (ref "C21") (pin "1") (pinfunction "1_1") (pintype "input"))
      (node (ref "H9") (pin "2") (pinfunction "2_2") (pintype "unspecified"))
      (node (ref "U3") (pin "4") (pinfunction "VCC_4") (pintype "unspecified"))
    )
    (net (code "33") (name "/VWIND") (class "Default")
      (node (ref "C22") (pin "2") (pinfunction "2_2") (pintype "unspecified"))
      (node (ref "C24") (pin "1") (pinfunction "1_1") (pintype "input"))
      (node (ref "H8") (pin "2") (pinfunction "2_2") (pintype "unspecified"))
      (node (ref "U8") (pin "4") (pinfunction "VCC_4") (pintype "unspecified"))
    )
    (net (code "34") (name "GND") (class "Default")
      (node (ref "C10") (pin "1") (pinfunction "1_1") (pintype "input"))
      (node (ref "C11") (pin "2") (pinfunction "2_2") (pintype "input"))
      (node (ref "C12") (pin "1") (pinfunction "1_1") (pintype "input"))
      (node (ref "C13") (pin "2") (pinfunction "2_2") (pintype "unspecified"))
      (node (ref "C15") (pin "1") (pinfunction "1_1") (pintype "unspecified"))
      (node (ref "C17") (pin "1") (pinfunction "1_1") (pintype "unspecified"))
      (node (ref "C18") (pin "1") (pinfunction "1_1") (pintype "unspecified"))
      (node (ref "C2") (pin "1") (pinfunction "1_1") (pintype "unspecified"))
      (node (ref "C20") (pin "2") (pinfunction "2_2") (pintype "input"))
      (node (ref "C21") (pin "2") (pinfunction "2_2") (pintype "input"))
      (node (ref "C22") (pin "1") (pinfunction "1_1") (pintype "unspecified"))
      (node (ref "C24") (pin "2") (pinfunction "2_2") (pintype "input"))
      (node (ref "C26") (pin "1") (pinfunction "1_1") (pintype "unspecified"))
      (node (ref "C27") (pin "1") (pinfunction "1_1") (pintype "input"))
      (node (ref "C29") (pin "2") (pinfunction "2_2") (pintype "unspecified"))
      (node (ref "C30") (pin "2") (pinfunction "2_2") (pintype "unspecified"))
      (node (ref "C31") (pin "1") (pinfunction "1_1") (pintype "unspecified"))
      (node (ref "C35") (pin "1") (pinfunction "1_1") (pintype "unspecified"))
      (node (ref "C36") (pin "2") (pinfunction "2_2") (pintype "unspecified"))
      (node (ref "C42") (pin "1") (pinfunction "1_1") (pintype "unspecified"))
      (node (ref "C43") (pin "1") (pinfunction "1_1") (pintype "unspecified"))
      (node (ref "C44") (pin "1") (pinfunction "1_1") (pintype "unspecified"))
      (node (ref "C45") (pin "1") (pinfunction "1_1") (pintype "unspecified"))
      (node (ref "C5") (pin "2") (pinfunction "2_2") (pintype "input"))
      (node (ref "C8") (pin "2") (pinfunction "2_2") (pintype "unspecified"))
      (node (ref "C9") (pin "2") (pinfunction "2_2") (pintype "input"))
      (node (ref "H10") (pin "5") (pinfunction "5_5") (pintype "unspecified"))
      (node (ref "H11") (pin "2") (pinfunction "2_2") (pintype "unspecified"))
      (node (ref "LED1") (pin "1") (pinfunction "K_1") (pintype "unspecified"))
      (node (ref "LED2") (pin "1") (pinfunction "K_1") (pintype "unspecified"))
      (node (ref "LED3") (pin "1") (pinfunction "K_1") (pintype "unspecified"))
      (node (ref "Q1") (pin "1") (pinfunction "ADJ/GND_1") (pintype "unspecified"))
      (node (ref "R17") (pin "1") (pinfunction "1_1") (pintype "unspecified"))
      (node (ref "R2") (pin "1") (pinfunction "1_1") (pintype "unspecified"))
      (node (ref "R22") (pin "1") (pinfunction "1_1") (pintype "unspecified"))
      (node (ref "R3") (pin "1") (pinfunction "1_1") (pintype "unspecified"))
      (node (ref "R4") (pin "1") (pinfunction "1_1") (pintype "unspecified"))
      (node (ref "R7") (pin "1") (pinfunction "1_1") (pintype "unspecified"))
      (node (ref "U1") (pin "12") (pinfunction "VSSA_12") (pintype "unspecified"))
      (node (ref "U1") (pin "18") (pinfunction "VSS_4_18") (pintype "unspecified"))
      (node (ref "U1") (pin "31") (pinfunction "VSS_1_31") (pintype "unspecified"))
      (node (ref "U1") (pin "47") (pinfunction "VSS_2_47") (pintype "unspecified"))
      (node (ref "U1") (pin "63") (pinfunction "VSS_3_63") (pintype "unspecified"))
      (node (ref "U10") (pin "6") (pinfunction "GND_6") (pintype "unspecified"))
      (node (ref "U10") (pin "9") (pinfunction "PowerPAD_9") (pintype "unspecified"))
      (node (ref "U13") (pin "14") (pinfunction "14_14") (pintype "unspecified"))
      (node (ref "U14") (pin "2") (pinfunction "2_2") (pintype "unspecified"))
      (node (ref "U3") (pin "3") (pinfunction "GND_3") (pintype "unspecified"))
      (node (ref "U4") (pin "14") (pinfunction "GND_14") (pintype "unspecified"))
      (node (ref "U4") (pin "28") (pinfunction "GND_28") (pintype "unspecified"))
      (node (ref "U4") (pin "29") (pinfunction "EP_29") (pintype "unspecified"))
      (node (ref "U5") (pin "4") (pinfunction "GND_4") (pintype "unspecified"))
      (node (ref "U6") (pin "2") (pinfunction "GND_2") (pintype "unspecified"))
      (node (ref "U7") (pin "3") (pinfunction "GND_3") (pintype "unspecified"))
      (node (ref "U8") (pin "3") (pinfunction "GND_3") (pintype "unspecified"))
      (node (ref "X2") (pin "2") (pinfunction "GND_2") (pintype "input"))
      (node (ref "X2") (pin "4") (pinfunction "GND_4") (pintype "input"))
    )
    (net (code "35") (name "Net-(C16-Pad1)") (class "Default")
      (node (ref "C16") (pin "1") (pinfunction "1_1") (pintype "unspecified"))
      (node (ref "H2") (pin "2") (pinfunction "2_2") (pintype "unspecified"))
      (node (ref "U3") (pin "5") (pinfunction "FO_5") (pintype "unspecified"))
      (node (ref "U3") (pin "6") (pinfunction "FO_6") (pintype "unspecified"))
    )
    (net (code "36") (name "Net-(C16-Pad2)") (class "Default")
      (node (ref "C16") (pin "2") (pinfunction "2_2") (pintype "unspecified"))
      (node (ref "H2") (pin "1") (pinfunction "1_1") (pintype "unspecified"))
      (node (ref "U3") (pin "7") (pinfunction "BO_7") (pintype "unspecified"))
      (node (ref "U3") (pin "8") (pinfunction "BO_8") (pintype "unspecified"))
    )
    (net (code "37") (name "Net-(C19-Pad1)") (class "Default")
      (node (ref "C19") (pin "1") (pinfunction "1_1") (pintype "unspecified"))
      (node (ref "H1") (pin "2") (pinfunction "2_2") (pintype "unspecified"))
      (node (ref "U7") (pin "5") (pinfunction "FO_5") (pintype "unspecified"))
      (node (ref "U7") (pin "6") (pinfunction "FO_6") (pintype "unspecified"))
    )
    (net (code "38") (name "Net-(C19-Pad2)") (class "Default")
      (node (ref "C19") (pin "2") (pinfunction "2_2") (pintype "unspecified"))
      (node (ref "H1") (pin "1") (pinfunction "1_1") (pintype "unspecified"))
      (node (ref "U7") (pin "7") (pinfunction "BO_7") (pintype "unspecified"))
      (node (ref "U7") (pin "8") (pinfunction "BO_8") (pintype "unspecified"))
    )
    (net (code "39") (name "Net-(C23-Pad1)") (class "Default")
      (node (ref "C23") (pin "1") (pinfunction "1_1") (pintype "unspecified"))
      (node (ref "H3") (pin "2") (pinfunction "2_2") (pintype "unspecified"))
      (node (ref "U8") (pin "5") (pinfunction "FO_5") (pintype "unspecified"))
      (node (ref "U8") (pin "6") (pinfunction "FO_6") (pintype "unspecified"))
    )
    (net (code "40") (name "Net-(C23-Pad2)") (class "Default")
      (node (ref "C23") (pin "2") (pinfunction "2_2") (pintype "unspecified"))
      (node (ref "H3") (pin "1") (pinfunction "1_1") (pintype "unspecified"))
      (node (ref "U8") (pin "7") (pinfunction "BO_7") (pintype "unspecified"))
      (node (ref "U8") (pin "8") (pinfunction "BO_8") (pintype "unspecified"))
    )
    (net (code "41") (name "Net-(LED1-A)") (class "Default")
      (node (ref "LED1") (pin "2") (pinfunction "A_2") (pintype "unspecified"))
      (node (ref "R19") (pin "1") (pinfunction "1_1") (pintype "input"))
    )
    (net (code "42") (name "Net-(LED2-A)") (class "Default")
      (node (ref "LED2") (pin "2") (pinfunction "A_2") (pintype "unspecified"))
      (node (ref "R21") (pin "1") (pinfunction "1_1") (pintype "unspecified"))
    )
    (net (code "43") (name "Net-(LED3-A)") (class "Default")
      (node (ref "LED3") (pin "2") (pinfunction "A_2") (pintype "unspecified"))
      (node (ref "R20") (pin "1") (pinfunction "1_1") (pintype "input"))
    )
    (net (code "44") (name "Net-(U1-BOOT0)") (class "Default")
      (node (ref "R22") (pin "2") (pinfunction "2_2") (pintype "unspecified"))
      (node (ref "U1") (pin "60") (pinfunction "BOOT0_60") (pintype "unspecified"))
    )
    (net (code "45") (name "Net-(U1-NRST)") (class "Default")
      (node (ref "R23") (pin "2") (pinfunction "2_2") (pintype "unspecified"))
      (node (ref "U1") (pin "7") (pinfunction "NRST_7") (pintype "unspecified"))
    )
    (net (code "46") (name "Net-(U3-BI)") (class "Default")
      (node (ref "R9") (pin "2") (pinfunction "2_2") (pintype "input"))
      (node (ref "U3") (pin "1") (pinfunction "BI_1") (pintype "unspecified"))
    )
    (net (code "47") (name "Net-(U3-FI)") (class "Default")
      (node (ref "R10") (pin "2") (pinfunction "2_2") (pintype "input"))
      (node (ref "U3") (pin "2") (pinfunction "FI_2") (pintype "unspecified"))
    )
    (net (code "48") (name "Net-(U4-AVREF)") (class "Default")
      (node (ref "R4") (pin "2") (pinfunction "2_2") (pintype "unspecified"))
      (node (ref "U4") (pin "12") (pinfunction "AVREF_12") (pintype "unspecified"))
      (node (ref "U4") (pin "13") (pinfunction "BVREF_13") (pintype "unspecified"))
    )
    (net (code "49") (name "Net-(U4-CP1)") (class "Default")
      (node (ref "C6") (pin "1") (pinfunction "1_1") (pintype "input"))
      (node (ref "U4") (pin "1") (pinfunction "CP1_1") (pintype "unspecified"))
    )
    (net (code "50") (name "Net-(U4-CP2)") (class "Default")
      (node (ref "C6") (pin "2") (pinfunction "2_2") (pintype "input"))
      (node (ref "U4") (pin "2") (pinfunction "CP2_2") (pintype "unspecified"))
    )
    (net (code "51") (name "Net-(U4-ISENA)") (class "Default")
      (node (ref "R2") (pin "2") (pinfunction "2_2") (pintype "unspecified"))
      (node (ref "U4") (pin "6") (pinfunction "ISENA_6") (pintype "unspecified"))
    )
    (net (code "52") (name "Net-(U4-ISENB)") (class "Default")
      (node (ref "R3") (pin "2") (pinfunction "2_2") (pintype "unspecified"))
      (node (ref "U4") (pin "9") (pinfunction "ISENB_9") (pintype "unspecified"))
    )
    (net (code "53") (name "Net-(U4-V3P3OUT)") (class "Default")
      (node (ref "C10") (pin "2") (pinfunction "2_2") (pintype "input"))
      (node (ref "U4") (pin "15") (pinfunction "V3P3OUT_15") (pintype "unspecified"))
    )
    (net (code "54") (name "Net-(U4-VCP)") (class "Default")
      (node (ref "C7") (pin "2") (pinfunction "2_2") (pintype "unspecified"))
      (node (ref "R1") (pin "2") (pinfunction "2_2") (pintype "input"))
      (node (ref "U4") (pin "3") (pinfunction "VCP_3") (pintype "unspecified"))
    )
    (net (code "55") (name "Net-(U6-SW)") (class "Default")
      (node (ref "L1") (pin "2") (pinfunction "2_2") (pintype "unspecified"))
      (node (ref "U11") (pin "2") (pinfunction "2_2") (pintype "unspecified"))
      (node (ref "U6") (pin "1") (pinfunction "SW_1") (pintype "unspecified"))
    )
    (net (code "56") (name "Net-(U7-BI)") (class "Default")
      (node (ref "R11") (pin "2") (pinfunction "2_2") (pintype "input"))
      (node (ref "U7") (pin "1") (pinfunction "BI_1") (pintype "unspecified"))
    )
    (net (code "57") (name "Net-(U7-FI)") (class "Default")
      (node (ref "R12") (pin "2") (pinfunction "2_2") (pintype "input"))
      (node (ref "U7") (pin "2") (pinfunction "FI_2") (pintype "unspecified"))
    )
    (net (code "58") (name "Net-(U8-BI)") (class "Default")
      (node (ref "R13") (pin "2") (pinfunction "2_2") (pintype "input"))
      (node (ref "U8") (pin "1") (pinfunction "BI_1") (pintype "unspecified"))
    )
    (net (code "59") (name "Net-(U8-FI)") (class "Default")
      (node (ref "R14") (pin "2") (pinfunction "2_2") (pintype "input"))
      (node (ref "U8") (pin "2") (pinfunction "FI_2") (pintype "unspecified"))
    )
    (net (code "60") (name "Net-(U10-BOOT)") (class "Default")
      (node (ref "C28") (pin "1") (pinfunction "1_1") (pintype "input"))
      (node (ref "U10") (pin "1") (pinfunction "BOOT_1") (pintype "unspecified"))
    )
    (net (code "61") (name "Net-(U10-PH)") (class "Default")
      (node (ref "C28") (pin "2") (pinfunction "2_2") (pintype "input"))
      (node (ref "L2") (pin "1") (pinfunction "1_1") (pintype "unspecified"))
      (node (ref "U10") (pin "8") (pinfunction "PH_8") (pintype "unspecified"))
    )
    (net (code "62") (name "Net-(U10-VIN)") (class "Default")
      (node (ref "C26") (pin "2") (pinfunction "2_2") (pintype "unspecified"))
      (node (ref "C27") (pin "2") (pinfunction "2_2") (pintype "input"))
      (node (ref "U10") (pin "7") (pinfunction "VIN_7") (pintype "unspecified"))
      (node (ref "U12") (pin "1") (pinfunction "1_1") (pintype "unspecified"))
    )
    (net (code "63") (name "Net-(U10-VSENSE)") (class "Default")
      (node (ref "R17") (pin "2") (pinfunction "2_2") (pintype "unspecified"))
      (node (ref "R18") (pin "1") (pinfunction "1_1") (pintype "unspecified"))
      (node (ref "U10") (pin "4") (pinfunction "VSENSE_4") (pintype "unspecified"))
    )
    (net (code "64") (name "unconnected-(U1-PA4-Pad20)") (class "Default")
      (node (ref "U1") (pin "20") (pinfunction "PA4_20") (pintype "unspecified"))
    )
    (net (code "65") (name "unconnected-(U1-PA12-Pad45)") (class "Default")
      (node (ref "U1") (pin "45") (pinfunction "PA12_45") (pintype "unspecified"))
    )
    (net (code "66") (name "unconnected-(U1-PA13-Pad46)") (class "Default")
      (node (ref "U1") (pin "46") (pinfunction "PA13_46") (pintype "unspecified"))
    )
    (net (code "67") (name "unconnected-(U1-PA14-Pad49)") (class "Default")
      (node (ref "U1") (pin "49") (pinfunction "PA14_49") (pintype "unspecified"))
    )
    (net (code "68") (name "unconnected-(U1-PA15-Pad50)") (class "Default")
      (node (ref "U1") (pin "50") (pinfunction "PA15_50") (pintype "unspecified"))
    )
    (net (code "69") (name "unconnected-(U1-PB0-Pad26)") (class "Default")
      (node (ref "U1") (pin "26") (pinfunction "PB0_26") (pintype "unspecified"))
    )
    (net (code "70") (name "unconnected-(U1-PB1-Pad27)") (class "Default")
      (node (ref "U1") (pin "27") (pinfunction "PB1_27") (pintype "unspecified"))
    )
    (net (code "71") (name "unconnected-(U1-PB2-Pad28)") (class "Default")
      (node (ref "U1") (pin "28") (pinfunction "PB2_28") (pintype "unspecified"))
    )
    (net (code "72") (name "unconnected-(U1-PB3-Pad55)") (class "Default")
      (node (ref "U1") (pin "55") (pinfunction "PB3_55") (pintype "unspecified"))
    )
    (net (code "73") (name "unconnected-(U1-PB4-Pad56)") (class "Default")
      (node (ref "U1") (pin "56") (pinfunction "PB4_56") (pintype "unspecified"))
    )
    (net (code "74") (name "unconnected-(U1-PB5-Pad57)") (class "Default")
      (node (ref "U1") (pin "57") (pinfunction "PB5_57") (pintype "unspecified"))
    )
    (net (code "75") (name "unconnected-(U1-PB9-Pad62)") (class "Default")
      (node (ref "U1") (pin "62") (pinfunction "PB9_62") (pintype "unspecified"))
    )
    (net (code "76") (name "unconnected-(U1-PB12-Pad33)") (class "Default")
      (node (ref "U1") (pin "33") (pinfunction "PB12_33") (pintype "unspecified"))
    )
    (net (code "77") (name "unconnected-(U1-PB13-Pad34)") (class "Default")
      (node (ref "U1") (pin "34") (pinfunction "PB13_34") (pintype "unspecified"))
    )
    (net (code "78") (name "unconnected-(U1-PB14-Pad35)") (class "Default")
      (node (ref "U1") (pin "35") (pinfunction "PB14_35") (pintype "unspecified"))
    )
    (net (code "79") (name "unconnected-(U1-PC0-Pad8)") (class "Default")
      (node (ref "U1") (pin "8") (pinfunction "PC0_8") (pintype "unspecified"))
    )
    (net (code "80") (name "unconnected-(U1-PC1-Pad9)") (class "Default")
      (node (ref "U1") (pin "9") (pinfunction "PC1_9") (pintype "unspecified"))
    )
    (net (code "81") (name "unconnected-(U1-PC2-Pad10)") (class "Default")
      (node (ref "U1") (pin "10") (pinfunction "PC2_10") (pintype "unspecified"))
    )
    (net (code "82") (name "unconnected-(U1-PC3-Pad11)") (class "Default")
      (node (ref "U1") (pin "11") (pinfunction "PC3_11") (pintype "unspecified"))
    )
    (net (code "83") (name "unconnected-(U1-PC5-Pad25)") (class "Default")
      (node (ref "U1") (pin "25") (pinfunction "PC5_25") (pintype "unspecified"))
    )
    (net (code "84") (name "unconnected-(U1-PC7-Pad38)") (class "Default")
      (node (ref "U1") (pin "38") (pinfunction "PC7_38") (pintype "unspecified"))
    )
    (net (code "85") (name "unconnected-(U1-PC8-Pad39)") (class "Default")
      (node (ref "U1") (pin "39") (pinfunction "PC8_39") (pintype "unspecified"))
    )
    (net (code "86") (name "unconnected-(U1-PC9-Pad40)") (class "Default")
      (node (ref "U1") (pin "40") (pinfunction "PC9_40") (pintype "unspecified"))
    )
    (net (code "87") (name "unconnected-(U1-PC10-Pad51)") (class "Default")
      (node (ref "U1") (pin "51") (pinfunction "PC10_51") (pintype "unspecified"))
    )
    (net (code "88") (name "unconnected-(U1-PC11-Pad52)") (class "Default")
      (node (ref "U1") (pin "52") (pinfunction "PC11_52") (pintype "unspecified"))
    )
    (net (code "89") (name "unconnected-(U1-PC12-Pad53)") (class "Default")
      (node (ref "U1") (pin "53") (pinfunction "PC12_53") (pintype "unspecified"))
    )
    (net (code "90") (name "unconnected-(U1-PC13-TAMPER-RTC-Pad2)") (class "Default")
      (node (ref "U1") (pin "2") (pinfunction "PC13-TAMPER-RTC_2") (pintype "unspecified+no_connect"))
    )
    (net (code "91") (name "unconnected-(U1-PC14-OSC32_IN-Pad3)") (class "Default")
      (node (ref "U1") (pin "3") (pinfunction "PC14-OSC32_IN_3") (pintype "unspecified+no_connect"))
    )
    (net (code "92") (name "unconnected-(U1-PC15-OSC32_OUT-Pad4)") (class "Default")
      (node (ref "U1") (pin "4") (pinfunction "PC15-OSC32_OUT_4") (pintype "unspecified+no_connect"))
    )
    (net (code "93") (name "unconnected-(U1-PD2-Pad54)") (class "Default")
      (node (ref "U1") (pin "54") (pinfunction "PD2_54") (pintype "unspecified"))
    )
    (net (code "94") (name "unconnected-(U4-DECAY-Pad19)") (class "Default")
      (node (ref "U4") (pin "19") (pinfunction "DECAY_19") (pintype "unspecified+no_connect"))
    )
    (net (code "95") (name "unconnected-(U4-MODE0-Pad24)") (class "Default")
      (node (ref "U4") (pin "24") (pinfunction "MODE0_24") (pintype "unspecified+no_connect"))
    )
    (net (code "96") (name "unconnected-(U4-MODE1-Pad25)") (class "Default")
      (node (ref "U4") (pin "25") (pinfunction "MODE1_25") (pintype "unspecified+no_connect"))
    )
    (net (code "97") (name "unconnected-(U4-MODE2-Pad26)") (class "Default")
      (node (ref "U4") (pin "26") (pinfunction "MODE2_26") (pintype "unspecified+no_connect"))
    )
    (net (code "98") (name "unconnected-(U4-NC-Pad23)") (class "Default")
      (node (ref "U4") (pin "23") (pinfunction "NC_23") (pintype "unspecified+no_connect"))
    )
    (net (code "99") (name "unconnected-(U4-NENBL-Pad21)") (class "Default")
      (node (ref "U4") (pin "21") (pinfunction "NENBL_21") (pintype "unspecified+no_connect"))
    )
    (net (code "100") (name "unconnected-(U4-nFAULT-Pad18)") (class "Default")
      (node (ref "U4") (pin "18") (pinfunction "nFAULT_18") (pintype "unspecified+no_connect"))
    )
    (net (code "101") (name "unconnected-(U4-nHOME-Pad27)") (class "Default")
      (node (ref "U4") (pin "27") (pinfunction "nHOME_27") (pintype "unspecified+no_connect"))
    )
    (net (code "102") (name "unconnected-(U10-ENA-Pad5)") (class "Default")
      (node (ref "U10") (pin "5") (pinfunction "ENA_5") (pintype "unspecified+no_connect"))
    )
    (net (code "103") (name "unconnected-(U10-NC-Pad2)") (class "Default")
      (node (ref "U10") (pin "2") (pinfunction "NC_2") (pintype "unspecified+no_connect"))
    )
    (net (code "104") (name "unconnected-(U10-NC-Pad3)") (class "Default")
      (node (ref "U10") (pin "3") (pinfunction "NC_3") (pintype "unspecified+no_connect"))
    )
    (net (code "105") (name "unconnected-(U13-Pad1)") (class "Default")
      (node (ref "U13") (pin "1") (pinfunction "1_1") (pintype "unspecified+no_connect"))
    )
    (net (code "106") (name "unconnected-(U13-Pad2)") (class "Default")
      (node (ref "U13") (pin "2") (pinfunction "2_2") (pintype "unspecified+no_connect"))
    )
    (net (code "107") (name "unconnected-(U13-Pad3)") (class "Default")
      (node (ref "U13") (pin "3") (pinfunction "3_3") (pintype "unspecified+no_connect"))
    )
    (net (code "108") (name "unconnected-(U13-Pad4)") (class "Default")
      (node (ref "U13") (pin "4") (pinfunction "4_4") (pintype "unspecified+no_connect"))
    )
    (net (code "109") (name "unconnected-(U13-Pad5)") (class "Default")
      (node (ref "U13") (pin "5") (pinfunction "5_5") (pintype "unspecified+no_connect"))
    )
    (net (code "110") (name "unconnected-(U13-Pad6)") (class "Default")
      (node (ref "U13") (pin "6") (pinfunction "6_6") (pintype "unspecified+no_connect"))
    )
    (net (code "111") (name "unconnected-(U13-Pad7)") (class "Default")
      (node (ref "U13") (pin "7") (pinfunction "7_7") (pintype "unspecified+no_connect"))
    )
    (net (code "112") (name "unconnected-(U13-Pad8)") (class "Default")
      (node (ref "U13") (pin "8") (pinfunction "8_8") (pintype "unspecified+no_connect"))
    )
    (net (code "113") (name "unconnected-(U13-Pad9)") (class "Default")
      (node (ref "U13") (pin "9") (pinfunction "9_9") (pintype "unspecified+no_connect"))
    )
    (net (code "114") (name "unconnected-(U13-Pad10)") (class "Default")
      (node (ref "U13") (pin "10") (pinfunction "10_10") (pintype "unspecified+no_connect"))
    )
    (net (code "115") (name "unconnected-(U13-Pad11)") (class "Default")
      (node (ref "U13") (pin "11") (pinfunction "11_11") (pintype "unspecified+no_connect"))
    )
    (net (code "116") (name "unconnected-(U13-Pad12)") (class "Default")
      (node (ref "U13") (pin "12") (pinfunction "12_12") (pintype "unspecified+no_connect"))
    )
    (net (code "117") (name "unconnected-(U13-Pad13)") (class "Default")
      (node (ref "U13") (pin "13") (pinfunction "13_13") (pintype "unspecified+no_connect"))
    )
    (net (code "118") (name "unconnected-(U14-Pad1)") (class "Default")
      (node (ref "U14") (pin "1") (pinfunction "1_1") (pintype "unspecified+no_connect"))
    )
    (net (code "119") (name "unconnected-(U14-Pad3)") (class "Default")
      (node (ref "U14") (pin "3") (pinfunction "3_3") (pintype "unspecified+no_connect"))
    )
    (net (code "120") (name "unconnected-(U14-Pad4)") (class "Default")
      (node (ref "U14") (pin "4") (pinfunction "4_4") (pintype "unspecified+no_connect"))
    )
    (net (code "121") (name "unconnected-(U14-Pad5)") (class "Default")
      (node (ref "U14") (pin "5") (pinfunction "5_5") (pintype "unspecified+no_connect"))
    )
    (net (code "122") (name "unconnected-(U14-Pad8)") (class "Default")
      (node (ref "U14") (pin "8") (pinfunction "8_8") (pintype "unspecified+no_connect"))
    )
    (net (code "123") (name "unconnected-(U14-Pad9)") (class "Default")
      (node (ref "U14") (pin "9") (pinfunction "9_9") (pintype "unspecified+no_connect"))
    )
    (net (code "124") (name "unconnected-(U14-Pad10)") (class "Default")
      (node (ref "U14") (pin "10") (pinfunction "10_10") (pintype "unspecified+no_connect"))
    )
    (net (code "125") (name "unconnected-(U14-Pad11)") (class "Default")
      (node (ref "U14") (pin "11") (pinfunction "11_11") (pintype "unspecified+no_connect"))
    )
    (net (code "126") (name "unconnected-(U14-Pad14)") (class "Default")
      (node (ref "U14") (pin "14") (pinfunction "14_14") (pintype "unspecified+no_connect"))
    )
    (net (code "127") (name "unconnected-(U14-Pad15)") (class "Default")
      (node (ref "U14") (pin "15") (pinfunction "15_15") (pintype "unspecified+no_connect"))
    )
  )
)
